# Single_V1.net
KiCad netlist of a schematic drawn in Altium Designer
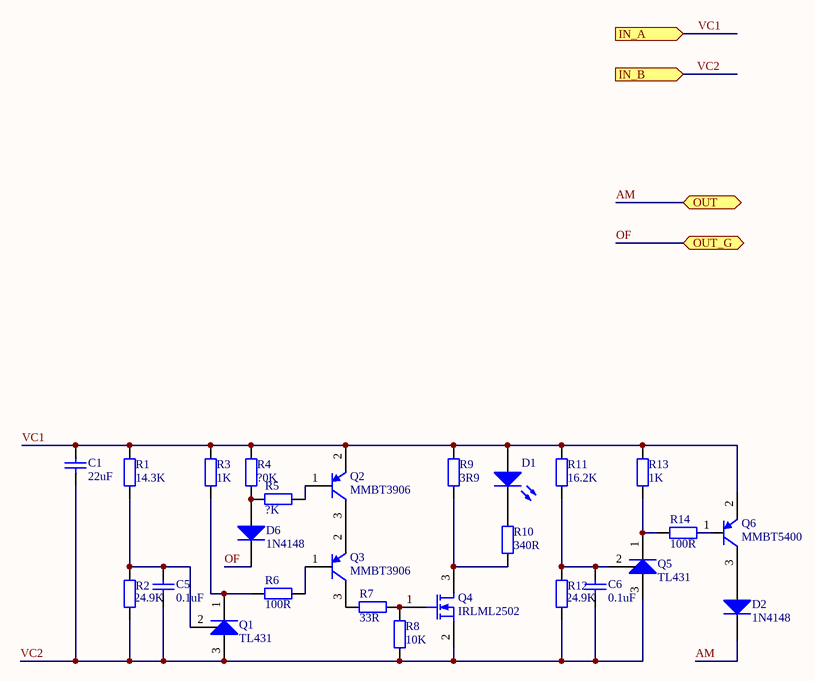
[diagram p0: Single_V1.SchDoc]

(export (version "E")
  (design (tool "Eeschema 10.0.6"))
  (components
    (comp (ref "C1")
      (value "22uF")
      (footprint "C-0603")
      (description "贴片瓷片电容")
      (fields (field (name "Comment") "Cap-S") (field (name "PUBLISHER") "Altium Limited"))
      (libsource (lib "fszhang") (part "Cap-S"))
    )
    (comp (ref "C5")
      (value "0.1uF")
      (footprint "C-0603")
      (description "贴片瓷片电容")
      (fields (field (name "Comment") "Cap-S") (field (name "PUBLISHER") "Altium Limited"))
      (libsource (lib "fszhang") (part "Cap-S"))
    )
    (comp (ref "C6")
      (value "0.1uF")
      (footprint "C-0603")
      (description "贴片瓷片电容")
      (fields (field (name "Comment") "Cap-S") (field (name "PUBLISHER") "Altium Limited"))
      (libsource (lib "fszhang") (part "Cap-S"))
    )
    (comp (ref "D1")
      (value "LED0")
      (footprint "LED-0805")
      (description "发光二极管")
      (fields (field (name "PUBLISHER") "Altium Limited"))
      (libsource (lib "fszhang") (part "LED0"))
    )
    (comp (ref "D2")
      (value "1N4148")
      (footprint "LED-0805")
      (description "整流二极管")
      (fields (field (name "PUBLISHER") "Altium Limited"))
      (libsource (lib "Fszhang") (part "Diode-R"))
    )
    (comp (ref "D6")
      (value "1N4148")
      (footprint "LED-0805")
      (description "整流二极管")
      (fields (field (name "PUBLISHER") "Altium Limited"))
      (libsource (lib "Fszhang") (part "Diode-R"))
    )
    (comp (ref "Q1")
      (value "TL431")
      (footprint "SOT23-3")
      (description "可控精密稳压源")
      (libsource (lib "fszhang") (part "TL431"))
    )
    (comp (ref "Q2")
      (value "MMBT3906")
      (footprint "SOT23-3")
      (description "贴片三极管")
      (fields (field (name "PUBLISHER") "Altium Limited"))
      (libsource (lib "Fszhang") (part "PNP1"))
    )
    (comp (ref "Q3")
      (value "MMBT3906")
      (footprint "SOT23-3")
      (description "贴片三极管")
      (fields (field (name "PUBLISHER") "Altium Limited"))
      (libsource (lib "Fszhang") (part "PNP1"))
    )
    (comp (ref "Q4")
      (value "IRLML2502")
      (footprint "SOT23-3")
      (description "MOSFET")
      (fields (field (name "PUBLISHER") "Altium Limited"))
      (libsource (lib "Fszhang") (part "MOSFET-N1"))
    )
    (comp (ref "Q5")
      (value "TL431")
      (footprint "SOT23-3")
      (description "可控精密稳压源")
      (libsource (lib "fszhang") (part "TL431"))
    )
    (comp (ref "Q6")
      (value "MMBT5400")
      (footprint "SOT23-3")
      (description "贴片三极管")
      (fields (field (name "PUBLISHER") "Altium Limited"))
      (libsource (lib "Fszhang") (part "PNP1"))
    )
    (comp (ref "R1")
      (value "14.3K")
      (footprint "0603-1")
      (description "贴片电阻")
      (fields (field (name "Comment") "Res1") (field (name "PUBLISHER") "Altium Limited"))
      (libsource (lib "Fszhang") (part "Res1"))
    )
    (comp (ref "R2")
      (value "24.9K")
      (footprint "0603-1")
      (description "贴片电阻")
      (fields (field (name "Comment") "Res1") (field (name "PUBLISHER") "Altium Limited"))
      (libsource (lib "Fszhang") (part "Res1"))
    )
    (comp (ref "R3")
      (value "1K")
      (footprint "0603-1")
      (description "贴片电阻")
      (fields (field (name "Comment") "Res1") (field (name "PUBLISHER") "Altium Limited"))
      (libsource (lib "Fszhang") (part "Res1"))
    )
    (comp (ref "R4")
      (value "?0K")
      (footprint "0603-1")
      (description "贴片电阻")
      (fields (field (name "Comment") "Res1") (field (name "PUBLISHER") "Altium Limited"))
      (libsource (lib "") (part "Res1_3"))
    )
    (comp (ref "R5")
      (value "?K")
      (footprint "0603-1")
      (description "贴片电阻")
      (fields (field (name "Comment") "Res1") (field (name "PUBLISHER") "Altium Limited"))
      (libsource (lib "") (part "Res1_1"))
    )
    (comp (ref "R6")
      (value "100R")
      (footprint "0603-1")
      (description "贴片电阻")
      (fields (field (name "Comment") "Res1") (field (name "PUBLISHER") "Altium Limited"))
      (libsource (lib "") (part "Res1_1"))
    )
    (comp (ref "R7")
      (value "33R")
      (footprint "0603-1")
      (description "贴片电阻")
      (fields (field (name "Comment") "Res1") (field (name "PUBLISHER") "Altium Limited"))
      (libsource (lib "") (part "Res1_2"))
    )
    (comp (ref "R8")
      (value "10K")
      (footprint "0603-1")
      (description "贴片电阻")
      (fields (field (name "Comment") "Res1") (field (name "PUBLISHER") "Altium Limited"))
      (libsource (lib "Fszhang") (part "Res1"))
    )
    (comp (ref "R9")
      (value "3R9")
      (footprint "AXIAL-1.0")
      (description "贴片电阻")
      (fields (field (name "Comment") "Res1") (field (name "PUBLISHER") "Altium Limited"))
      (libsource (lib "Fszhang") (part "Res1"))
    )
    (comp (ref "R10")
      (value "340R")
      (footprint "0603-1")
      (description "贴片电阻")
      (fields (field (name "Comment") "Res1") (field (name "PUBLISHER") "Altium Limited"))
      (libsource (lib "Fszhang") (part "Res1"))
    )
    (comp (ref "R11")
      (value "16.2K")
      (footprint "0603-1")
      (description "贴片电阻")
      (fields (field (name "Comment") "Res1") (field (name "PUBLISHER") "Altium Limited"))
      (libsource (lib "Fszhang") (part "Res1"))
    )
    (comp (ref "R12")
      (value "24.9K")
      (footprint "0603-1")
      (description "贴片电阻")
      (fields (field (name "Comment") "Res1") (field (name "PUBLISHER") "Altium Limited"))
      (libsource (lib "Fszhang") (part "Res1"))
    )
    (comp (ref "R13")
      (value "1K")
      (footprint "0603-1")
      (description "贴片电阻")
      (fields (field (name "Comment") "Res1") (field (name "PUBLISHER") "Altium Limited"))
      (libsource (lib "Fszhang") (part "Res1"))
    )
    (comp (ref "R14")
      (value "100R")
      (footprint "0603-1")
      (description "贴片电阻")
      (fields (field (name "Comment") "Res1") (field (name "PUBLISHER") "Altium Limited"))
      (libsource (lib "") (part "Res1_1"))
    )
  )
  (nets
    (net (code "1") (name "/AM") (class "Default")
      (node (ref "D2") (pin "2") (pinfunction "K_2") (pintype "passive"))
    )
    (net (code "2") (name "/OF") (class "Default")
      (node (ref "D6") (pin "2") (pinfunction "K_2") (pintype "passive"))
    )
    (net (code "3") (name "/VC1") (class "Default")
      (node (ref "C1") (pin "2") (pinfunction "2_2") (pintype "passive"))
      (node (ref "D1") (pin "1") (pinfunction "A_1") (pintype "passive"))
      (node (ref "Q2") (pin "2") (pinfunction "E_2") (pintype "passive"))
      (node (ref "Q6") (pin "2") (pinfunction "E_2") (pintype "passive"))
      (node (ref "R1") (pin "2") (pinfunction "2_2") (pintype "passive"))
      (node (ref "R11") (pin "2") (pinfunction "2_2") (pintype "passive"))
      (node (ref "R13") (pin "2") (pinfunction "2_2") (pintype "passive"))
      (node (ref "R3") (pin "2") (pinfunction "2_2") (pintype "passive"))
      (node (ref "R4") (pin "1") (pinfunction "1_1") (pintype "passive"))
      (node (ref "R9") (pin "2") (pinfunction "2_2") (pintype "passive"))
    )
    (net (code "4") (name "/VC2") (class "Default")
      (node (ref "C1") (pin "1") (pinfunction "1_1") (pintype "passive"))
      (node (ref "C5") (pin "1") (pinfunction "1_1") (pintype "passive"))
      (node (ref "C6") (pin "1") (pinfunction "1_1") (pintype "passive"))
      (node (ref "Q1") (pin "3") (pinfunction "A_3") (pintype "passive"))
      (node (ref "Q4") (pin "2") (pinfunction "S_2") (pintype "passive"))
      (node (ref "Q5") (pin "3") (pinfunction "A_3") (pintype "passive"))
      (node (ref "R12") (pin "1") (pinfunction "1_1") (pintype "passive"))
      (node (ref "R2") (pin "1") (pinfunction "1_1") (pintype "passive"))
      (node (ref "R8") (pin "1") (pinfunction "1_1") (pintype "passive"))
    )
    (net (code "5") (name "Net-(D1-K)") (class "Default")
      (node (ref "D1") (pin "2") (pinfunction "K_2") (pintype "passive"))
      (node (ref "R10") (pin "2") (pinfunction "2_2") (pintype "passive"))
    )
    (net (code "6") (name "Net-(D2-A)") (class "Default")
      (node (ref "D2") (pin "1") (pinfunction "A_1") (pintype "passive"))
      (node (ref "Q6") (pin "3") (pinfunction "C_3") (pintype "passive"))
    )
    (net (code "7") (name "Net-(D6-A)") (class "Default")
      (node (ref "D6") (pin "1") (pinfunction "A_1") (pintype "passive"))
      (node (ref "R4") (pin "2") (pinfunction "2_2") (pintype "passive"))
      (node (ref "R5") (pin "2") (pinfunction "2_2") (pintype "passive"))
    )
    (net (code "8") (name "Net-(Q1-K)") (class "Default")
      (node (ref "Q1") (pin "1") (pinfunction "K_1") (pintype "passive"))
      (node (ref "R3") (pin "1") (pinfunction "1_1") (pintype "passive"))
      (node (ref "R6") (pin "2") (pinfunction "2_2") (pintype "passive"))
    )
    (net (code "9") (name "Net-(Q1-R)") (class "Default")
      (node (ref "C5") (pin "2") (pinfunction "2_2") (pintype "passive"))
      (node (ref "Q1") (pin "2") (pinfunction "R_2") (pintype "passive"))
      (node (ref "R1") (pin "1") (pinfunction "1_1") (pintype "passive"))
      (node (ref "R2") (pin "2") (pinfunction "2_2") (pintype "passive"))
    )
    (net (code "10") (name "Net-(Q2-B)") (class "Default")
      (node (ref "Q2") (pin "1") (pinfunction "B_1") (pintype "passive"))
      (node (ref "R5") (pin "1") (pinfunction "1_1") (pintype "passive"))
    )
    (net (code "11") (name "Net-(Q2-C)") (class "Default")
      (node (ref "Q2") (pin "3") (pinfunction "C_3") (pintype "passive"))
      (node (ref "Q3") (pin "2") (pinfunction "E_2") (pintype "passive"))
    )
    (net (code "12") (name "Net-(Q3-B)") (class "Default")
      (node (ref "Q3") (pin "1") (pinfunction "B_1") (pintype "passive"))
      (node (ref "R6") (pin "1") (pinfunction "1_1") (pintype "passive"))
    )
    (net (code "13") (name "Net-(Q3-C)") (class "Default")
      (node (ref "Q3") (pin "3") (pinfunction "C_3") (pintype "passive"))
      (node (ref "R7") (pin "1") (pinfunction "1_1") (pintype "passive"))
    )
    (net (code "14") (name "Net-(Q4-D)") (class "Default")
      (node (ref "Q4") (pin "3") (pinfunction "D_3") (pintype "passive"))
      (node (ref "R10") (pin "1") (pinfunction "1_1") (pintype "passive"))
      (node (ref "R9") (pin "1") (pinfunction "1_1") (pintype "passive"))
    )
    (net (code "15") (name "Net-(Q4-G)") (class "Default")
      (node (ref "Q4") (pin "1") (pinfunction "G_1") (pintype "passive"))
      (node (ref "R7") (pin "2") (pinfunction "2_2") (pintype "passive"))
      (node (ref "R8") (pin "2") (pinfunction "2_2") (pintype "passive"))
    )
    (net (code "16") (name "Net-(Q5-K)") (class "Default")
      (node (ref "Q5") (pin "1") (pinfunction "K_1") (pintype "passive"))
      (node (ref "R13") (pin "1") (pinfunction "1_1") (pintype "passive"))
      (node (ref "R14") (pin "2") (pinfunction "2_2") (pintype "passive"))
    )
    (net (code "17") (name "Net-(Q5-R)") (class "Default")
      (node (ref "C6") (pin "2") (pinfunction "2_2") (pintype "passive"))
      (node (ref "Q5") (pin "2") (pinfunction "R_2") (pintype "passive"))
      (node (ref "R11") (pin "1") (pinfunction "1_1") (pintype "passive"))
      (node (ref "R12") (pin "2") (pinfunction "2_2") (pintype "passive"))
    )
    (net (code "18") (name "Net-(Q6-B)") (class "Default")
      (node (ref "Q6") (pin "1") (pinfunction "B_1") (pintype "passive"))
      (node (ref "R14") (pin "1") (pinfunction "1_1") (pintype "passive"))
    )
  )
)
